# power_rails.net
KiCad netlist of a schematic drawn in Altium Designer
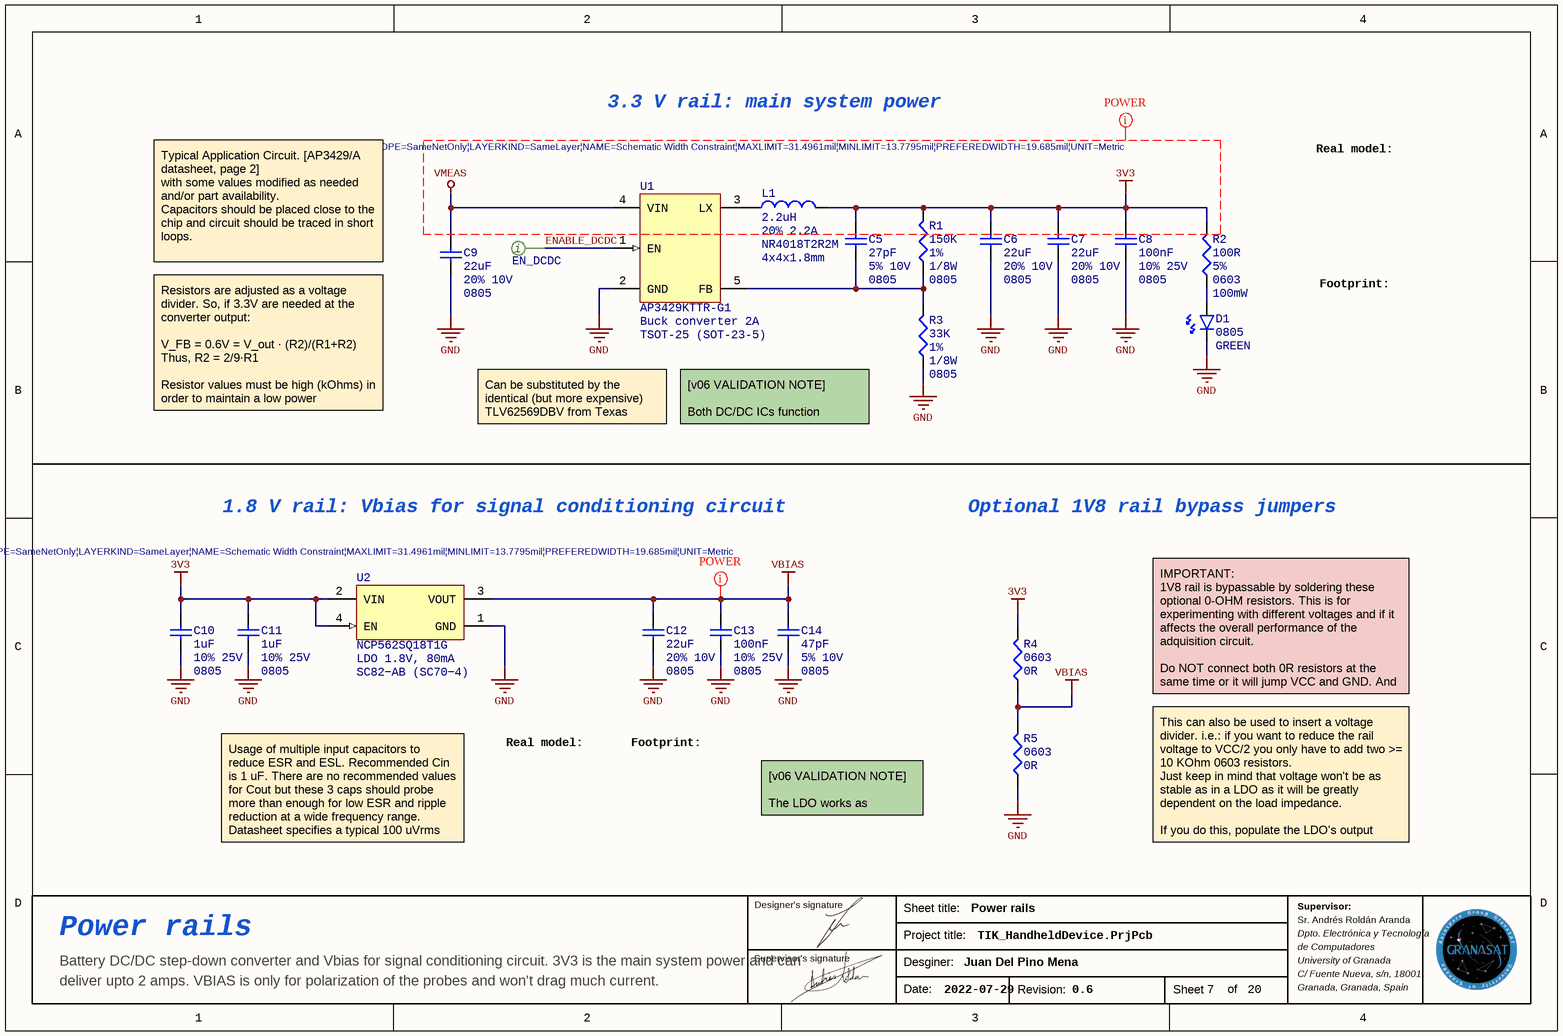
[diagram p0: power_rails.SchDoc]

(export (version "E")
  (design (tool "Eeschema 10.0.6"))
  (components
    (comp (ref "C5")
      (value "27pF")
      (footprint "CAP 0805_2012")
      (description "Ceramic cap size 0805")
      (fields
        (field (name "TOLERANCE") "5% 10V")
        (field (name "PACKAGEDESCRIPTION") "0805")
        (field (name "Comment") "Cap_cer_0805")
      )
      (libsource (lib "tik_handheld_schlib") (part "Cap_cer_0805_27pF_5%"))
    )
    (comp (ref "C6")
      (value "22uF")
      (footprint "CAP 0805_2012")
      (description "Ceramic cap size 0805 CC0805MKX5R6BB226 Yageo MLCC 22uF 10V 20% X5R")
      (fields
        (field (name "TOLERANCE") "20% 10V")
        (field (name "PACKAGEDESCRIPTION") "0805")
        (field (name "Comment") "Cap_cer_0805")
      )
      (libsource (lib "tik_handheld_schlib") (part "Cap_cer_0805_22uF_20%"))
    )
    (comp (ref "C7")
      (value "22uF")
      (footprint "CAP 0805_2012")
      (description "Ceramic cap size 0805 CC0805MKX5R6BB226 Yageo MLCC 22uF 10V 20% X5R")
      (fields
        (field (name "TOLERANCE") "20% 10V")
        (field (name "PACKAGEDESCRIPTION") "0805")
        (field (name "Comment") "Cap_cer_0805")
      )
      (libsource (lib "tik_handheld_schlib") (part "Cap_cer_0805_22uF_20%"))
    )
    (comp (ref "C8")
      (value "100nF")
      (footprint "CAP 0805_2012")
      (description "Ceramic cap size 0805")
      (fields
        (field (name "TOLERANCE") "10% 25V")
        (field (name "PACKAGEDESCRIPTION") "0805")
        (field (name "Comment") "Cap_cer_0805")
      )
      (libsource (lib "tik_handheld_schlib") (part "Cap_cer_0805_100nF_10%"))
    )
    (comp (ref "C9")
      (value "22uF")
      (footprint "CAP 0805_2012")
      (description "Ceramic cap size 0805 CC0805MKX5R6BB226 Yageo MLCC 22uF 10V 20% X5R")
      (fields
        (field (name "TOLERANCE") "20% 10V")
        (field (name "PACKAGEDESCRIPTION") "0805")
        (field (name "Comment") "Cap_cer_0805")
      )
      (libsource (lib "tik_handheld_schlib") (part "Cap_cer_0805_22uF_20%"))
    )
    (comp (ref "C10")
      (value "1uF")
      (footprint "CAP 0805_2012")
      (description "Ceramic cap size 0805")
      (fields
        (field (name "TOLERANCE") "10% 25V")
        (field (name "PACKAGEDESCRIPTION") "0805")
        (field (name "Comment") "Cap_cer_0805")
      )
      (libsource (lib "tik_handheld_schlib") (part "Cap_cer_0805_1uF_10%"))
    )
    (comp (ref "C11")
      (value "1uF")
      (footprint "CAP 0805_2012")
      (description "Ceramic cap size 0805")
      (fields
        (field (name "TOLERANCE") "10% 25V")
        (field (name "PACKAGEDESCRIPTION") "0805")
        (field (name "Comment") "Cap_cer_0805")
      )
      (libsource (lib "tik_handheld_schlib") (part "Cap_cer_0805_1uF_10%"))
    )
    (comp (ref "C12")
      (value "22uF")
      (footprint "CAP 0805_2012")
      (description "Ceramic cap size 0805 CC0805MKX5R6BB226 Yageo MLCC 22uF 10V 20% X5R")
      (fields
        (field (name "TOLERANCE") "20% 10V")
        (field (name "PACKAGEDESCRIPTION") "0805")
        (field (name "Comment") "Cap_cer_0805")
      )
      (libsource (lib "tik_handheld_schlib") (part "Cap_cer_0805_22uF_20%"))
    )
    (comp (ref "C13")
      (value "100nF")
      (footprint "CAP 0805_2012")
      (description "Ceramic cap size 0805")
      (fields
        (field (name "TOLERANCE") "10% 25V")
        (field (name "PACKAGEDESCRIPTION") "0805")
        (field (name "Comment") "Cap_cer_0805")
      )
      (libsource (lib "tik_handheld_schlib") (part "Cap_cer_0805_100nF_10%"))
    )
    (comp (ref "C14")
      (value "47pF")
      (footprint "CAP 0805_2012")
      (description "Ceramic cap size 0805")
      (fields
        (field (name "TOLERANCE") "5% 10V")
        (field (name "PACKAGEDESCRIPTION") "0805")
        (field (name "Comment") "Cap_cer_0805")
      )
      (libsource (lib "tik_handheld_schlib") (part "Cap_cer_0805_47pF_5%"))
    )
    (comp (ref "D1")
      (value "Diode LED_G_0805")
      (footprint "LED 0805_2012 GREEN")
      (description "Low power LED color Green")
      (fields (field (name "PACKAGEDESCRIPTION") "0805") (field (name "TYPE") "GREEN"))
      (libsource (lib "tik_handheld_schlib") (part "Diode LED_G_0805"))
    )
    (comp (ref "EN_DCDC")
      (value "Test Point Pad dual sided")
      (footprint "TEST POINT PAD")
      (description "Test point - PCB Pad dual sided")
      (libsource (lib "tik_handheld_schlib") (part "Test Point Pad dual sided"))
    )
    (comp (ref "L1")
      (value "2.2uH")
      (footprint "Inductor 4x4mm")
      (description "Shielded Power Inductor 2.2 uH 20% 2.2 A 50.4 mohms 3.11 A (sat) 60MHz \r\n4018: 4x4x1.8mm")
      (fields
        (field (name "TOLERANCE") "20% 2.2A")
        (field (name "PART") "NR4018T2R2M")
        (field (name "PACKAGEDESCRIPTION") "4x4x1.8mm")
        (field (name "Comment") "Ind 2uH_Wire_Shield_2A_4x4")
      )
      (libsource (lib "tik_handheld_schlib") (part "Ind 2uH_Wire_Shield_2A_4x4"))
    )
    (comp (ref "R1")
      (value "150K")
      (footprint "RES 0805_2012")
      (description "Res size 0805 SMD mounting, low power\r\nYageo-RC0805FR-07150KL")
      (fields
        (field (name "TOLERANCE") "1%")
        (field (name "POWERDISIPATED") "1/8W")
        (field (name "PACKAGEDESCRIPTION") "0805")
        (field (name "Comment") "Res_0805_150K_1%_1/8W")
      )
      (libsource (lib "tik_handheld_schlib") (part "Res_0805_150K_1%_1/8W"))
    )
    (comp (ref "R2")
      (value "100R")
      (footprint "RES 0603_1608")
      (description "Res size 0603 SMD mounting, low power")
      (fields
        (field (name "TOLERANCE") "5%")
        (field (name "PACKAGEDESCRIPTION") "0603")
        (field (name "POWERDISIPATED") "100mW")
        (field (name "Comment") "Res_0603_100R_5%_100mW")
      )
      (libsource (lib "tik_handheld_schlib") (part "Res_0603_100R_5%_100mW"))
    )
    (comp (ref "R3")
      (value "33K")
      (footprint "RES 0805_2012")
      (description "Res size 0805 SMD mounting, low power")
      (fields
        (field (name "TOLERANCE") "1%")
        (field (name "POWERDISIPATED") "1/8W")
        (field (name "PACKAGEDESCRIPTION") "0805")
        (field (name "Comment") "Res_0805_33K_1%_1/8W")
      )
      (libsource (lib "tik_handheld_schlib") (part "Res_0805_33K_1%_1/8W"))
    )
    (comp (ref "R4")
      (value "0R")
      (footprint "RES 0603_1608")
      (description "Res size 0603 SMD mounting, zero-ohm 0R Yageo RC0603JR-070RL")
      (fields
        (field (name "TOLERANCE") "5%")
        (field (name "PACKAGEDESCRIPTION") "0603")
        (field (name "Comment") "Res_0603_0ohm")
      )
      (libsource (lib "tik_handheld_schlib") (part "Res_0603_0ohm"))
    )
    (comp (ref "R5")
      (value "0R")
      (footprint "RES 0603_1608")
      (description "Res size 0603 SMD mounting, zero-ohm 0R Yageo RC0603JR-070RL")
      (fields
        (field (name "TOLERANCE") "5%")
        (field (name "PACKAGEDESCRIPTION") "0603")
        (field (name "Comment") "Res_0603_0ohm")
      )
      (libsource (lib "tik_handheld_schlib") (part "Res_0603_0ohm"))
    )
    (comp (ref "U1")
      (value "AP3429_A")
      (footprint "SOT-23-5 AP3429")
      (description "1.0MHZ, 2A STEP-DOWN DC-DC BUCK CONVERTER, with latch-off protection")
      (fields
        (field (name "PART") "AP3429KTTR-G1")
        (field (name "TYPE") "Buck converter 2A")
        (field (name "PACKAGEDESCRIPTION") "TSOT-25 (SOT-23-5)")
      )
      (libsource (lib "tik_handheld_schlib") (part "IC AP3429_A dcdc buck"))
    )
    (comp (ref "U2")
      (value "LDO 1.8V, 80mA")
      (footprint "SC70-5 LT SC82-AB NCP562")
      (description "Fixed output lowdropout linear regulator.\r\n1.8 V 80 mA")
      (fields
        (field (name "PART") "NCP562SQ18T1G")
        (field (name "PACKAGEDESCRIPTION") "SC82−AB (SC70−4)")
        (field (name "Comment") "IC NCP562SQ18T1G LDO")
      )
      (libsource (lib "tik_handheld_schlib") (part "IC NCP562SQ18T1G LDO"))
    )
  )
  (nets
    (net (code "1") (name "/ENABLE_DCDC") (class "Default")
      (node (ref "EN_DCDC") (pin "1") (pinfunction "1_1") (pintype "passive"))
      (node (ref "U1") (pin "1") (pinfunction "EN_1") (pintype "input"))
    )
    (net (code "2") (name "3V3") (class "Default")
      (node (ref "C10") (pin "2") (pinfunction "2_2") (pintype "passive"))
      (node (ref "C11") (pin "2") (pinfunction "2_2") (pintype "passive"))
      (node (ref "C5") (pin "2") (pinfunction "2_2") (pintype "passive"))
      (node (ref "C6") (pin "2") (pinfunction "2_2") (pintype "passive"))
      (node (ref "C7") (pin "2") (pinfunction "2_2") (pintype "passive"))
      (node (ref "C8") (pin "2") (pinfunction "2_2") (pintype "passive"))
      (node (ref "L1") (pin "2") (pinfunction "2_2") (pintype "passive"))
      (node (ref "R1") (pin "2") (pinfunction "2_2") (pintype "passive"))
      (node (ref "R2") (pin "2") (pinfunction "2_2") (pintype "passive"))
      (node (ref "R4") (pin "2") (pinfunction "2_2") (pintype "passive"))
      (node (ref "U2") (pin "2") (pinfunction "VIN_2") (pintype "power_in"))
      (node (ref "U2") (pin "4") (pinfunction "EN_4") (pintype "input"))
    )
    (net (code "3") (name "GND") (class "Default")
      (node (ref "C10") (pin "1") (pinfunction "1_1") (pintype "passive"))
      (node (ref "C11") (pin "1") (pinfunction "1_1") (pintype "passive"))
      (node (ref "C12") (pin "1") (pinfunction "1_1") (pintype "passive"))
      (node (ref "C13") (pin "1") (pinfunction "1_1") (pintype "passive"))
      (node (ref "C14") (pin "1") (pinfunction "1_1") (pintype "passive"))
      (node (ref "C6") (pin "1") (pinfunction "1_1") (pintype "passive"))
      (node (ref "C7") (pin "1") (pinfunction "1_1") (pintype "passive"))
      (node (ref "C8") (pin "1") (pinfunction "1_1") (pintype "passive"))
      (node (ref "C9") (pin "1") (pinfunction "1_1") (pintype "passive"))
      (node (ref "D1") (pin "2") (pinfunction "2_2") (pintype "passive"))
      (node (ref "R3") (pin "1") (pinfunction "1_1") (pintype "passive"))
      (node (ref "R5") (pin "1") (pinfunction "1_1") (pintype "passive"))
      (node (ref "U1") (pin "2") (pinfunction "GND_2") (pintype "power_in"))
      (node (ref "U2") (pin "1") (pinfunction "GND_1") (pintype "passive"))
    )
    (net (code "4") (name "Net-(D1-Pad1)") (class "Default")
      (node (ref "D1") (pin "1") (pinfunction "1_1") (pintype "passive"))
      (node (ref "R2") (pin "1") (pinfunction "1_1") (pintype "passive"))
    )
    (net (code "5") (name "Net-(U1-FB)") (class "Default")
      (node (ref "C5") (pin "1") (pinfunction "1_1") (pintype "passive"))
      (node (ref "R1") (pin "1") (pinfunction "1_1") (pintype "passive"))
      (node (ref "R3") (pin "2") (pinfunction "2_2") (pintype "passive"))
      (node (ref "U1") (pin "5") (pinfunction "FB_5") (pintype "power_in"))
    )
    (net (code "6") (name "Net-(U1-LX)") (class "Default")
      (node (ref "L1") (pin "1") (pinfunction "1_1") (pintype "passive"))
      (node (ref "U1") (pin "3") (pinfunction "LX_3") (pintype "power_in"))
    )
    (net (code "7") (name "VBIAS") (class "Default")
      (node (ref "C12") (pin "2") (pinfunction "2_2") (pintype "passive"))
      (node (ref "C13") (pin "2") (pinfunction "2_2") (pintype "passive"))
      (node (ref "C14") (pin "2") (pinfunction "2_2") (pintype "passive"))
      (node (ref "R4") (pin "1") (pinfunction "1_1") (pintype "passive"))
      (node (ref "R5") (pin "2") (pinfunction "2_2") (pintype "passive"))
      (node (ref "U2") (pin "3") (pinfunction "VOUT_3") (pintype "power_in"))
    )
    (net (code "8") (name "VMEAS") (class "Default")
      (node (ref "C9") (pin "2") (pinfunction "2_2") (pintype "passive"))
      (node (ref "U1") (pin "4") (pinfunction "VIN_4") (pintype "power_in"))
    )
  )
)
